# adcBreakout.net
KiCad netlist of a schematic drawn in EAGLE
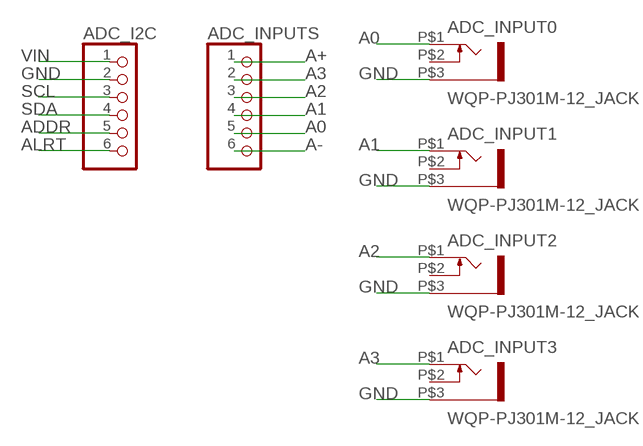
[diagram p0: schematic, sheet 1]

(export (version "E")
  (design (tool "Eeschema 10.0.6"))
  (components
    (comp (ref "ADC_I2C")
      (value "PINHD-1X6B")
      (footprint "eagle-import:1X06-BIG")
      (libsource (lib "eagle-import") (part "PINHD-1X6B"))
    )
    (comp (ref "ADC_INPUT0")
      (value "WQP-PJ301M-12_JACK")
      (footprint "eagle-import:WQP-PJ301M-12_JACK")
      (libsource (lib "eagle-import") (part "WQP-PJ301M-12_JACK"))
    )
    (comp (ref "ADC_INPUT1")
      (value "WQP-PJ301M-12_JACK")
      (footprint "eagle-import:WQP-PJ301M-12_JACK")
      (libsource (lib "eagle-import") (part "WQP-PJ301M-12_JACK"))
    )
    (comp (ref "ADC_INPUT2")
      (value "WQP-PJ301M-12_JACK")
      (footprint "eagle-import:WQP-PJ301M-12_JACK")
      (libsource (lib "eagle-import") (part "WQP-PJ301M-12_JACK"))
    )
    (comp (ref "ADC_INPUT3")
      (value "WQP-PJ301M-12_JACK")
      (footprint "eagle-import:WQP-PJ301M-12_JACK")
      (libsource (lib "eagle-import") (part "WQP-PJ301M-12_JACK"))
    )
    (comp (ref "ADC_INPUTS")
      (value "PINHD-1X6B")
      (footprint "eagle-import:1X06-BIG")
      (libsource (lib "eagle-import") (part "PINHD-1X6B"))
    )
  )
  (nets
    (net (code "1") (name "/A+") (class "Default")
      (node (ref "ADC_INPUTS") (pin "1") (pinfunction "1_1") (pintype "passive"))
    )
    (net (code "2") (name "/A-") (class "Default")
      (node (ref "ADC_INPUTS") (pin "6") (pinfunction "6_6") (pintype "passive"))
    )
    (net (code "3") (name "/A0") (class "Default")
      (node (ref "ADC_INPUT0") (pin "P$1") (pinfunction "2_P$1") (pintype "passive"))
      (node (ref "ADC_INPUTS") (pin "5") (pinfunction "5_5") (pintype "passive"))
    )
    (net (code "4") (name "/A1") (class "Default")
      (node (ref "ADC_INPUT1") (pin "P$1") (pinfunction "2_P$1") (pintype "passive"))
      (node (ref "ADC_INPUTS") (pin "4") (pinfunction "4_4") (pintype "passive"))
    )
    (net (code "5") (name "/A2") (class "Default")
      (node (ref "ADC_INPUT2") (pin "P$1") (pinfunction "2_P$1") (pintype "passive"))
      (node (ref "ADC_INPUTS") (pin "3") (pinfunction "3_3") (pintype "passive"))
    )
    (net (code "6") (name "/A3") (class "Default")
      (node (ref "ADC_INPUT3") (pin "P$1") (pinfunction "2_P$1") (pintype "passive"))
      (node (ref "ADC_INPUTS") (pin "2") (pinfunction "2_2") (pintype "passive"))
    )
    (net (code "7") (name "/ADDR") (class "Default")
      (node (ref "ADC_I2C") (pin "5") (pinfunction "5_5") (pintype "passive"))
    )
    (net (code "8") (name "/ALRT") (class "Default")
      (node (ref "ADC_I2C") (pin "6") (pinfunction "6_6") (pintype "passive"))
    )
    (net (code "9") (name "/GND") (class "Default")
      (node (ref "ADC_I2C") (pin "2") (pinfunction "2_2") (pintype "passive"))
      (node (ref "ADC_INPUT0") (pin "P$3") (pinfunction "1_P$3") (pintype "passive"))
      (node (ref "ADC_INPUT1") (pin "P$3") (pinfunction "1_P$3") (pintype "passive"))
      (node (ref "ADC_INPUT2") (pin "P$3") (pinfunction "1_P$3") (pintype "passive"))
      (node (ref "ADC_INPUT3") (pin "P$3") (pinfunction "1_P$3") (pintype "passive"))
    )
    (net (code "10") (name "/SCL") (class "Default")
      (node (ref "ADC_I2C") (pin "3") (pinfunction "3_3") (pintype "passive"))
    )
    (net (code "11") (name "/SDA") (class "Default")
      (node (ref "ADC_I2C") (pin "4") (pinfunction "4_4") (pintype "passive"))
    )
    (net (code "12") (name "/VIN") (class "Default")
      (node (ref "ADC_I2C") (pin "1") (pinfunction "1_1") (pintype "passive"))
    )
    (net (code "13") (name "unconnected-(ADC_INPUT0-3-PadP$2)") (class "Default")
      (node (ref "ADC_INPUT0") (pin "P$2") (pinfunction "3_P$2") (pintype "passive"))
    )
    (net (code "14") (name "unconnected-(ADC_INPUT1-3-PadP$2)") (class "Default")
      (node (ref "ADC_INPUT1") (pin "P$2") (pinfunction "3_P$2") (pintype "passive"))
    )
    (net (code "15") (name "unconnected-(ADC_INPUT2-3-PadP$2)") (class "Default")
      (node (ref "ADC_INPUT2") (pin "P$2") (pinfunction "3_P$2") (pintype "passive"))
    )
    (net (code "16") (name "unconnected-(ADC_INPUT3-3-PadP$2)") (class "Default")
      (node (ref "ADC_INPUT3") (pin "P$2") (pinfunction "3_P$2") (pintype "passive"))
    )
  )
)
